# a_Conventional_Boost.net
KiCad netlist of a schematic drawn in EAGLE
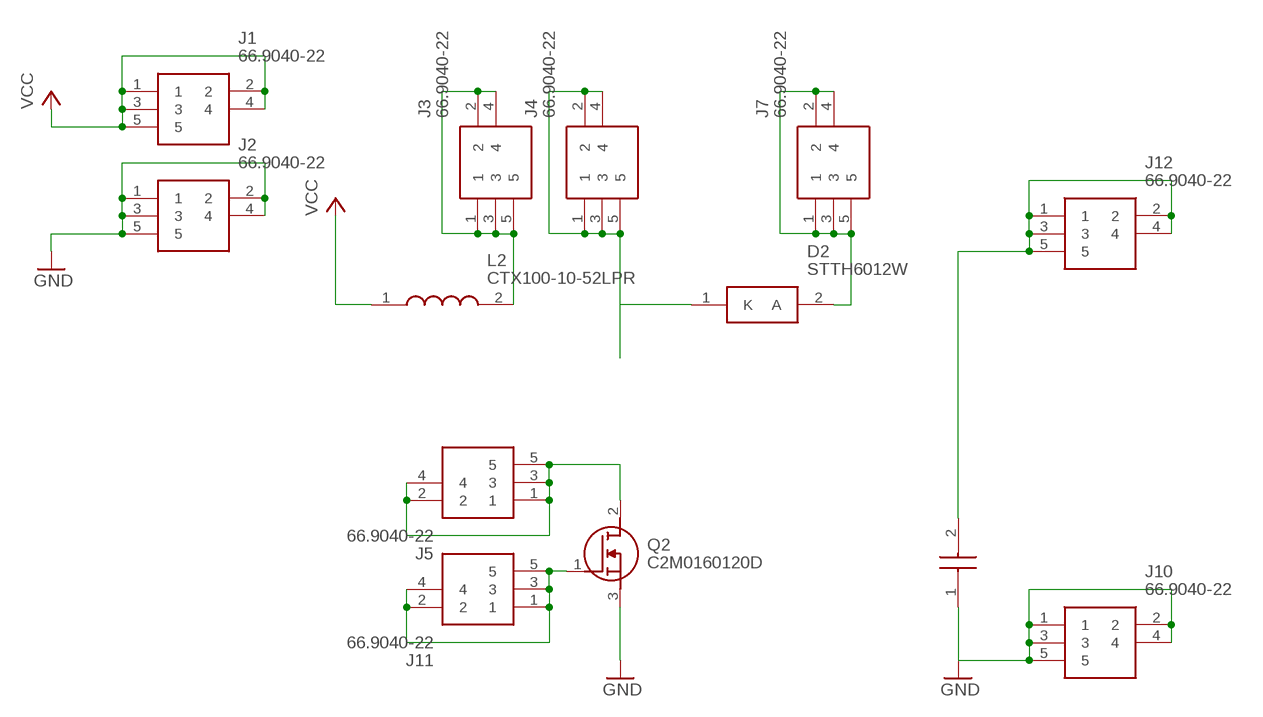
[diagram p0: schematic, sheet 1]

(export (version "E")
  (design (tool "Eeschema 10.0.6"))
  (components
    (comp (ref "D2")
      (value "STTH6012W")
      (footprint "eagle-import:TO1090P515X1560X2445-2P")
      (fields (field (name "RS_PART_NUMBER") "6870818"))
      (libsource (lib "eagle-import") (part "STTH6012W"))
    )
    (comp (ref "J1")
      (value "66.9040-22")
      (footprint "eagle-import:66904022")
      (libsource (lib "eagle-import") (part "66.9040-22"))
    )
    (comp (ref "J2")
      (value "66.9040-22")
      (footprint "eagle-import:66904022")
      (libsource (lib "eagle-import") (part "66.9040-22"))
    )
    (comp (ref "J3")
      (value "66.9040-22")
      (footprint "eagle-import:66904022")
      (libsource (lib "eagle-import") (part "66.9040-22"))
    )
    (comp (ref "J4")
      (value "66.9040-22")
      (footprint "eagle-import:66904022")
      (libsource (lib "eagle-import") (part "66.9040-22"))
    )
    (comp (ref "J5")
      (value "66.9040-22")
      (footprint "eagle-import:66904022")
      (libsource (lib "eagle-import") (part "66.9040-22"))
    )
    (comp (ref "J7")
      (value "66.9040-22")
      (footprint "eagle-import:66904022")
      (libsource (lib "eagle-import") (part "66.9040-22"))
    )
    (comp (ref "J10")
      (value "66.9040-22")
      (footprint "eagle-import:66904022")
      (libsource (lib "eagle-import") (part "66.9040-22"))
    )
    (comp (ref "J11")
      (value "66.9040-22")
      (footprint "eagle-import:66904022")
      (libsource (lib "eagle-import") (part "66.9040-22"))
    )
    (comp (ref "J12")
      (value "66.9040-22")
      (footprint "eagle-import:66904022")
      (libsource (lib "eagle-import") (part "66.9040-22"))
    )
    (comp (ref "L2")
      (value "CTX100-10-52LPR")
      (footprint "eagle-import:CTX1001052LPR")
      (libsource (lib "eagle-import") (part "CTX100-10-52LPR"))
    )
    (comp (ref "Q2")
      (value "C2M0160120D")
      (footprint "eagle-import:TO544P521X1594X2550-3P")
      (fields (field (name "RS_PART_NUMBER") "1629709"))
      (libsource (lib "eagle-import") (part "C2M0160120D"))
    )
    (comp (ref "U$1")
      (value "B32774D4505K000")
      (footprint "eagle-import:B32774D4505K000")
      (fields (field (name "RS_PART_NUMBER") "1726009"))
      (libsource (lib "eagle-import") (part "B32774D4505K000"))
    )
  )
  (nets
    (net (code "1") (name "GND") (class "Default")
      (node (ref "J10") (pin "1") (pinfunction "1_1") (pintype "bidirectional"))
      (node (ref "J10") (pin "2") (pinfunction "2_2") (pintype "bidirectional"))
      (node (ref "J10") (pin "3") (pinfunction "3_3") (pintype "bidirectional"))
      (node (ref "J10") (pin "4") (pinfunction "4_4") (pintype "bidirectional"))
      (node (ref "J10") (pin "5") (pinfunction "5_5") (pintype "bidirectional"))
      (node (ref "J2") (pin "1") (pinfunction "1_1") (pintype "bidirectional"))
      (node (ref "J2") (pin "2") (pinfunction "2_2") (pintype "bidirectional"))
      (node (ref "J2") (pin "3") (pinfunction "3_3") (pintype "bidirectional"))
      (node (ref "J2") (pin "4") (pinfunction "4_4") (pintype "bidirectional"))
      (node (ref "J2") (pin "5") (pinfunction "5_5") (pintype "bidirectional"))
      (node (ref "Q2") (pin "3") (pinfunction "S_3") (pintype "bidirectional"))
      (node (ref "U$1") (pin "1") (pinfunction "1_1") (pintype "bidirectional"))
    )
    (net (code "2") (name "Net-(D2-A)") (class "Default")
      (node (ref "D2") (pin "2") (pinfunction "A_2") (pintype "bidirectional"))
      (node (ref "J7") (pin "1") (pinfunction "1_1") (pintype "bidirectional"))
      (node (ref "J7") (pin "2") (pinfunction "2_2") (pintype "bidirectional"))
      (node (ref "J7") (pin "3") (pinfunction "3_3") (pintype "bidirectional"))
      (node (ref "J7") (pin "4") (pinfunction "4_4") (pintype "bidirectional"))
      (node (ref "J7") (pin "5") (pinfunction "5_5") (pintype "bidirectional"))
    )
    (net (code "3") (name "Net-(D2-K)") (class "Default")
      (node (ref "D2") (pin "1") (pinfunction "K_1") (pintype "bidirectional"))
      (node (ref "J4") (pin "1") (pinfunction "1_1") (pintype "bidirectional"))
      (node (ref "J4") (pin "2") (pinfunction "2_2") (pintype "bidirectional"))
      (node (ref "J4") (pin "3") (pinfunction "3_3") (pintype "bidirectional"))
      (node (ref "J4") (pin "4") (pinfunction "4_4") (pintype "bidirectional"))
      (node (ref "J4") (pin "5") (pinfunction "5_5") (pintype "bidirectional"))
    )
    (net (code "4") (name "Net-(J3-Pad1)") (class "Default")
      (node (ref "J3") (pin "1") (pinfunction "1_1") (pintype "bidirectional"))
      (node (ref "J3") (pin "2") (pinfunction "2_2") (pintype "bidirectional"))
      (node (ref "J3") (pin "3") (pinfunction "3_3") (pintype "bidirectional"))
      (node (ref "J3") (pin "4") (pinfunction "4_4") (pintype "bidirectional"))
      (node (ref "J3") (pin "5") (pinfunction "5_5") (pintype "bidirectional"))
      (node (ref "L2") (pin "2") (pinfunction "2_2") (pintype "bidirectional"))
    )
    (net (code "5") (name "Net-(J12-Pad1)") (class "Default")
      (node (ref "J12") (pin "1") (pinfunction "1_1") (pintype "bidirectional"))
      (node (ref "J12") (pin "2") (pinfunction "2_2") (pintype "bidirectional"))
      (node (ref "J12") (pin "3") (pinfunction "3_3") (pintype "bidirectional"))
      (node (ref "J12") (pin "4") (pinfunction "4_4") (pintype "bidirectional"))
      (node (ref "J12") (pin "5") (pinfunction "5_5") (pintype "bidirectional"))
      (node (ref "U$1") (pin "2") (pinfunction "2_2") (pintype "bidirectional"))
    )
    (net (code "6") (name "Net-(Q2-D)") (class "Default")
      (node (ref "J5") (pin "1") (pinfunction "1_1") (pintype "bidirectional"))
      (node (ref "J5") (pin "2") (pinfunction "2_2") (pintype "bidirectional"))
      (node (ref "J5") (pin "3") (pinfunction "3_3") (pintype "bidirectional"))
      (node (ref "J5") (pin "4") (pinfunction "4_4") (pintype "bidirectional"))
      (node (ref "J5") (pin "5") (pinfunction "5_5") (pintype "bidirectional"))
      (node (ref "Q2") (pin "2") (pinfunction "D_2") (pintype "bidirectional"))
    )
    (net (code "7") (name "Net-(Q2-G)") (class "Default")
      (node (ref "J11") (pin "1") (pinfunction "1_1") (pintype "bidirectional"))
      (node (ref "J11") (pin "2") (pinfunction "2_2") (pintype "bidirectional"))
      (node (ref "J11") (pin "3") (pinfunction "3_3") (pintype "bidirectional"))
      (node (ref "J11") (pin "4") (pinfunction "4_4") (pintype "bidirectional"))
      (node (ref "J11") (pin "5") (pinfunction "5_5") (pintype "bidirectional"))
      (node (ref "Q2") (pin "1") (pinfunction "G_1") (pintype "bidirectional"))
    )
    (net (code "8") (name "VCC") (class "Default")
      (node (ref "J1") (pin "1") (pinfunction "1_1") (pintype "bidirectional"))
      (node (ref "J1") (pin "2") (pinfunction "2_2") (pintype "bidirectional"))
      (node (ref "J1") (pin "3") (pinfunction "3_3") (pintype "bidirectional"))
      (node (ref "J1") (pin "4") (pinfunction "4_4") (pintype "bidirectional"))
      (node (ref "J1") (pin "5") (pinfunction "5_5") (pintype "bidirectional"))
      (node (ref "L2") (pin "1") (pinfunction "1_1") (pintype "bidirectional"))
    )
  )
)
